# 03_LCD.net
KiCad netlist of a schematic drawn in Altium Designer
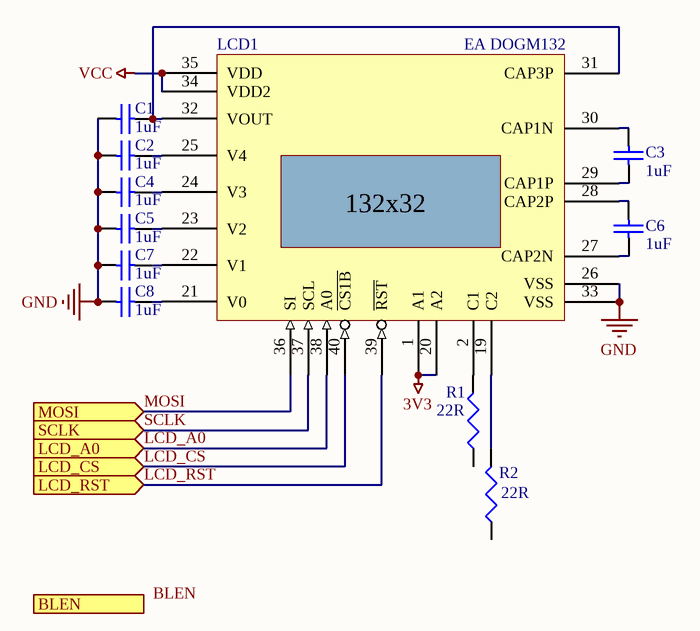
[diagram p0: [03] LCD.SchDoc]

(export (version "E")
  (design (tool "Eeschema 10.0.6"))
  (components
    (comp (ref "C1")
      (value "1uF")
      (footprint "1608[0603]")
      (description "Capacitor (Semiconductor SIM Model)")
      (fields (field (name "Comment") "Cap Semi") (field (name "PUBLISHER") "Altium Limited"))
      (libsource (lib "Miscellaneous Devices") (part "Cap Semi"))
    )
    (comp (ref "C2")
      (value "1uF")
      (footprint "1608[0603]")
      (description "Capacitor (Semiconductor SIM Model)")
      (fields (field (name "Comment") "Cap Semi") (field (name "PUBLISHER") "Altium Limited"))
      (libsource (lib "Miscellaneous Devices") (part "Cap Semi"))
    )
    (comp (ref "C3")
      (value "1uF")
      (footprint "1608[0603]")
      (description "Capacitor (Semiconductor SIM Model)")
      (fields (field (name "Comment") "Cap Semi") (field (name "PUBLISHER") "Altium Limited"))
      (libsource (lib "Miscellaneous Devices") (part "Cap Semi"))
    )
    (comp (ref "C4")
      (value "1uF")
      (footprint "1608[0603]")
      (description "Capacitor (Semiconductor SIM Model)")
      (fields (field (name "Comment") "Cap Semi") (field (name "PUBLISHER") "Altium Limited"))
      (libsource (lib "Miscellaneous Devices") (part "Cap Semi"))
    )
    (comp (ref "C5")
      (value "1uF")
      (footprint "1608[0603]")
      (description "Capacitor (Semiconductor SIM Model)")
      (fields (field (name "Comment") "Cap Semi") (field (name "PUBLISHER") "Altium Limited"))
      (libsource (lib "Miscellaneous Devices") (part "Cap Semi"))
    )
    (comp (ref "C6")
      (value "1uF")
      (footprint "1608[0603]")
      (description "Capacitor (Semiconductor SIM Model)")
      (fields (field (name "Comment") "Cap Semi") (field (name "PUBLISHER") "Altium Limited"))
      (libsource (lib "Miscellaneous Devices") (part "Cap Semi"))
    )
    (comp (ref "C7")
      (value "1uF")
      (footprint "1608[0603]")
      (description "Capacitor (Semiconductor SIM Model)")
      (fields (field (name "Comment") "Cap Semi") (field (name "PUBLISHER") "Altium Limited"))
      (libsource (lib "Miscellaneous Devices") (part "Cap Semi"))
    )
    (comp (ref "C8")
      (value "1uF")
      (footprint "1608[0603]")
      (description "Capacitor (Semiconductor SIM Model)")
      (fields (field (name "Comment") "Cap Semi") (field (name "PUBLISHER") "Altium Limited"))
      (libsource (lib "Miscellaneous Devices") (part "Cap Semi"))
    )
    (comp (ref "LCD1")
      (value "EA DOGM132")
      (footprint "EA DOGM132-5")
      (description "132x32 graphical LCD")
      (libsource (lib "6DOF IMU_ver1") (part "EA DOGM132"))
    )
    (comp (ref "R1")
      (value "22R")
      (footprint "J1-0603")
      (description "Resistor")
      (fields (field (name "Comment") "Res3") (field (name "PUBLISHER") "Altium Limited"))
      (libsource (lib "Miscellaneous Devices") (part "Res3"))
    )
    (comp (ref "R2")
      (value "22R")
      (footprint "J1-0603")
      (description "Resistor")
      (fields (field (name "Comment") "Res3") (field (name "PUBLISHER") "Altium Limited"))
      (libsource (lib "Miscellaneous Devices") (part "Res3"))
    )
  )
  (nets
    (net (code "2") (name "/LCD_A0") (class "Default")
      (node (ref "LCD1") (pin "38") (pinfunction "A0_38") (pintype "input"))
    )
    (net (code "3") (name "/LCD_CS") (class "Default")
      (node (ref "LCD1") (pin "40") (pinfunction "~{CS1B}_40") (pintype "input"))
    )
    (net (code "4") (name "/LCD_RST") (class "Default")
      (node (ref "LCD1") (pin "39") (pinfunction "~{RST}_39") (pintype "input"))
    )
    (net (code "5") (name "/MOSI") (class "Default")
      (node (ref "LCD1") (pin "36") (pinfunction "SI_36") (pintype "input"))
    )
    (net (code "6") (name "/SCLK") (class "Default")
      (node (ref "LCD1") (pin "37") (pinfunction "SCL_37") (pintype "input"))
    )
    (net (code "7") (name "3V3") (class "Default")
      (node (ref "LCD1") (pin "1") (pinfunction "A1_1") (pintype "passive"))
      (node (ref "LCD1") (pin "20") (pinfunction "A2_20") (pintype "passive"))
    )
    (net (code "8") (name "GND") (class "Default")
      (node (ref "C1") (pin "1") (pinfunction "1_1") (pintype "passive"))
      (node (ref "C2") (pin "1") (pinfunction "1_1") (pintype "passive"))
      (node (ref "C4") (pin "1") (pinfunction "1_1") (pintype "passive"))
      (node (ref "C5") (pin "1") (pinfunction "1_1") (pintype "passive"))
      (node (ref "C7") (pin "1") (pinfunction "1_1") (pintype "passive"))
      (node (ref "C8") (pin "1") (pinfunction "1_1") (pintype "passive"))
      (node (ref "LCD1") (pin "26") (pinfunction "VSS_26") (pintype "passive"))
      (node (ref "LCD1") (pin "33") (pinfunction "VSS_33") (pintype "passive"))
    )
    (net (code "9") (name "Net-(LCD1-C1)") (class "Default")
      (node (ref "LCD1") (pin "2") (pinfunction "C1_2") (pintype "passive"))
      (node (ref "R1") (pin "2") (pinfunction "2_2") (pintype "passive"))
    )
    (net (code "10") (name "Net-(LCD1-C2)") (class "Default")
      (node (ref "LCD1") (pin "19") (pinfunction "C2_19") (pintype "passive"))
      (node (ref "R2") (pin "2") (pinfunction "2_2") (pintype "passive"))
    )
    (net (code "11") (name "Net-(LCD1-CAP1N)") (class "Default")
      (node (ref "C3") (pin "1") (pinfunction "1_1") (pintype "passive"))
      (node (ref "LCD1") (pin "30") (pinfunction "CAP1N_30") (pintype "passive"))
    )
    (net (code "12") (name "Net-(LCD1-CAP1P)") (class "Default")
      (node (ref "C3") (pin "2") (pinfunction "2_2") (pintype "passive"))
      (node (ref "LCD1") (pin "29") (pinfunction "CAP1P_29") (pintype "passive"))
    )
    (net (code "13") (name "Net-(LCD1-CAP2N)") (class "Default")
      (node (ref "C6") (pin "2") (pinfunction "2_2") (pintype "passive"))
      (node (ref "LCD1") (pin "27") (pinfunction "CAP2N_27") (pintype "passive"))
    )
    (net (code "14") (name "Net-(LCD1-CAP2P)") (class "Default")
      (node (ref "C6") (pin "1") (pinfunction "1_1") (pintype "passive"))
      (node (ref "LCD1") (pin "28") (pinfunction "CAP2P_28") (pintype "passive"))
    )
    (net (code "15") (name "Net-(LCD1-CAP3P)") (class "Default")
      (node (ref "C1") (pin "2") (pinfunction "2_2") (pintype "passive"))
      (node (ref "LCD1") (pin "31") (pinfunction "CAP3P_31") (pintype "passive"))
      (node (ref "LCD1") (pin "32") (pinfunction "VOUT_32") (pintype "passive"))
    )
    (net (code "16") (name "Net-(LCD1-V0)") (class "Default")
      (node (ref "C8") (pin "2") (pinfunction "2_2") (pintype "passive"))
      (node (ref "LCD1") (pin "21") (pinfunction "V0_21") (pintype "passive"))
    )
    (net (code "17") (name "Net-(LCD1-V1)") (class "Default")
      (node (ref "C7") (pin "2") (pinfunction "2_2") (pintype "passive"))
      (node (ref "LCD1") (pin "22") (pinfunction "V1_22") (pintype "passive"))
    )
    (net (code "18") (name "Net-(LCD1-V2)") (class "Default")
      (node (ref "C5") (pin "2") (pinfunction "2_2") (pintype "passive"))
      (node (ref "LCD1") (pin "23") (pinfunction "V2_23") (pintype "passive"))
    )
    (net (code "19") (name "Net-(LCD1-V3)") (class "Default")
      (node (ref "C4") (pin "2") (pinfunction "2_2") (pintype "passive"))
      (node (ref "LCD1") (pin "24") (pinfunction "V3_24") (pintype "passive"))
    )
    (net (code "20") (name "Net-(LCD1-V4)") (class "Default")
      (node (ref "C2") (pin "2") (pinfunction "2_2") (pintype "passive"))
      (node (ref "LCD1") (pin "25") (pinfunction "V4_25") (pintype "passive"))
    )
    (net (code "21") (name "VCC") (class "Default")
      (node (ref "LCD1") (pin "34") (pinfunction "VDD2_34") (pintype "passive"))
      (node (ref "LCD1") (pin "35") (pinfunction "VDD_35") (pintype "passive"))
    )
    (net (code "22") (name "unconnected-(R1-Pad1)") (class "Default")
      (node (ref "R1") (pin "1") (pinfunction "1_1") (pintype "passive"))
    )
    (net (code "23") (name "unconnected-(R2-Pad1)") (class "Default")
      (node (ref "R2") (pin "1") (pinfunction "1_1") (pintype "passive"))
    )
  )
)
